# AMS_Slave_Controller.net
KiCad netlist of a schematic drawn in Altium Designer
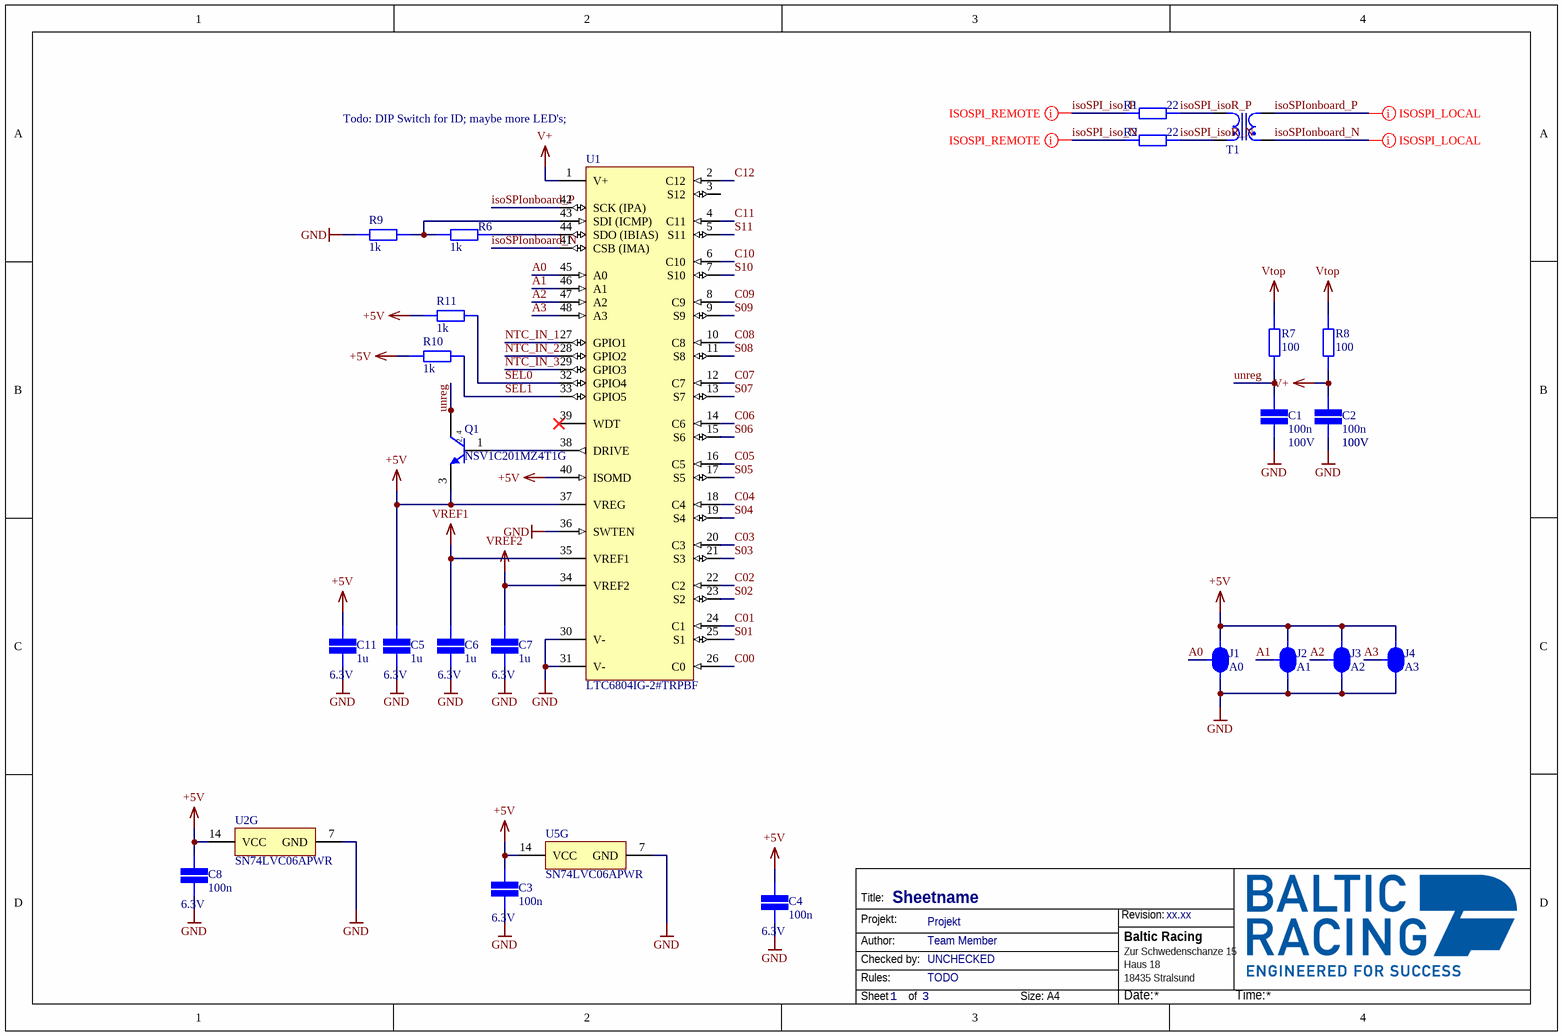
[diagram p0: AMS_Slave_Controller.SchDoc]

(export (version "E")
  (design (tool "Eeschema 10.0.6"))
  (components
    (comp (ref "C1")
      (value "100n")
      (footprint "CAP 0805/2012")
      (description "Capacitor with multiple Footprints")
      (fields (field (name "VOLTAGE") "100V") (field (name "Comment") "SMD Capacitor"))
      (libsource (lib "Standardbauteile") (part "SMD Capacitor"))
    )
    (comp (ref "C2")
      (value "100n")
      (footprint "CAP 0805/2012")
      (description "Capacitor with multiple Footprints")
      (fields (field (name "VOLTAGE") "100V") (field (name "Comment") "SMD Capacitor"))
      (libsource (lib "Standardbauteile") (part "SMD Capacitor"))
    )
    (comp (ref "C3")
      (value "100n")
      (footprint "CAP 0603/1608")
      (description "Capacitor with multiple Footprints")
      (fields (field (name "VOLTAGE") "6.3V") (field (name "Comment") "SMD Capacitor"))
      (libsource (lib "Standardbauteile") (part "SMD Capacitor"))
    )
    (comp (ref "C4")
      (value "100n")
      (footprint "CAP 0603/1608")
      (description "Capacitor with multiple Footprints")
      (fields (field (name "VOLTAGE") "6.3V") (field (name "Comment") "SMD Capacitor"))
      (libsource (lib "Standardbauteile") (part "SMD Capacitor"))
    )
    (comp (ref "C5")
      (value "1u")
      (footprint "CAP 0805/2012")
      (description "Capacitor with multiple Footprints")
      (fields (field (name "VOLTAGE") "6.3V") (field (name "Comment") "SMD Capacitor"))
      (libsource (lib "") (part "SMD Capacitor_1"))
    )
    (comp (ref "C6")
      (value "1u")
      (footprint "CAP 0805/2012")
      (description "Capacitor with multiple Footprints")
      (fields (field (name "VOLTAGE") "6.3V") (field (name "Comment") "SMD Capacitor"))
      (libsource (lib "") (part "SMD Capacitor_1"))
    )
    (comp (ref "C7")
      (value "1u")
      (footprint "CAP 0805/2012")
      (description "Capacitor with multiple Footprints")
      (fields (field (name "VOLTAGE") "6.3V") (field (name "Comment") "SMD Capacitor"))
      (libsource (lib "") (part "SMD Capacitor_1"))
    )
    (comp (ref "C8")
      (value "100n")
      (footprint "CAP 0603/1608")
      (description "Capacitor with multiple Footprints")
      (fields (field (name "VOLTAGE") "6.3V") (field (name "Comment") "SMD Capacitor"))
      (libsource (lib "Standardbauteile") (part "SMD Capacitor"))
    )
    (comp (ref "C11")
      (value "1u")
      (footprint "CAP 0805/2012")
      (description "Capacitor with multiple Footprints")
      (fields (field (name "VOLTAGE") "6.3V") (field (name "Comment") "SMD Capacitor"))
      (libsource (lib "") (part "SMD Capacitor_1"))
    )
    (comp (ref "J1")
      (value "A0")
      (footprint "SMD-JUMPER-3")
      (libsource (lib "Standardbauteile") (part "SMD Jumper 3"))
    )
    (comp (ref "J2")
      (value "A1")
      (footprint "SMD-JUMPER-3")
      (libsource (lib "Standardbauteile") (part "SMD Jumper 3"))
    )
    (comp (ref "J3")
      (value "A2")
      (footprint "SMD-JUMPER-3")
      (libsource (lib "Standardbauteile") (part "SMD Jumper 3"))
    )
    (comp (ref "J4")
      (value "A3")
      (footprint "SMD-JUMPER-3")
      (libsource (lib "Standardbauteile") (part "SMD Jumper 3"))
    )
    (comp (ref "Q1")
      (value "NSV1C201MZ4T1G")
      (footprint "ONSC-SOT-223-4-318E-04_V")
      (description "100 V, 2 A, Low VCE(sat), NPN Transistor, 4-Pin SOT-223, Pb-Free, Tape and Reel")
      (fields (field (name "MANUFACTURER") "On Semiconductor"))
      (libsource (lib "Altium Content Vault") (part "ONSC-NPN-B1C2E3C4-4"))
    )
    (comp (ref "R1")
      (value "22")
      (footprint "STACKPOLE CSR0603")
      (description "Resistor with multiple footprints")
      (fields (field (name "Comment") "SMD Resistor"))
      (libsource (lib "Standardbauteile") (part "SMD Resistor"))
    )
    (comp (ref "R2")
      (value "22")
      (footprint "STACKPOLE CSR0603")
      (description "Resistor with multiple footprints")
      (fields (field (name "Comment") "SMD Resistor"))
      (libsource (lib "Standardbauteile") (part "SMD Resistor"))
    )
    (comp (ref "R6")
      (value "1k")
      (footprint "STACKPOLE CSR0603")
      (description "Resistor with multiple footprints")
      (fields (field (name "Comment") "SMD Resistor"))
      (libsource (lib "Standardbauteile") (part "SMD Resistor"))
    )
    (comp (ref "R7")
      (value "100")
      (footprint "STACKPOLE CSR0603")
      (description "Resistor with multiple footprints")
      (fields (field (name "Comment") "SMD Resistor"))
      (libsource (lib "Standardbauteile") (part "SMD Resistor"))
    )
    (comp (ref "R8")
      (value "100")
      (footprint "STACKPOLE CSR0603")
      (description "Resistor with multiple footprints")
      (fields (field (name "Comment") "SMD Resistor"))
      (libsource (lib "Standardbauteile") (part "SMD Resistor"))
    )
    (comp (ref "R9")
      (value "1k")
      (footprint "STACKPOLE CSR0603")
      (description "Resistor with multiple footprints")
      (fields (field (name "Comment") "SMD Resistor"))
      (libsource (lib "Standardbauteile") (part "SMD Resistor"))
    )
    (comp (ref "R10")
      (value "1k")
      (footprint "STACKPOLE CSR0603")
      (description "Resistor with multiple footprints")
      (fields (field (name "Comment") "SMD Resistor"))
      (libsource (lib "Standardbauteile") (part "SMD Resistor"))
    )
    (comp (ref "R11")
      (value "1k")
      (footprint "STACKPOLE CSR0603")
      (description "Resistor with multiple footprints")
      (fields (field (name "Comment") "SMD Resistor"))
      (libsource (lib "Standardbauteile") (part "SMD Resistor"))
    )
    (comp (ref "T1")
      (value "750110055")
      (footprint "Wuerth_750110055")
      (description "Würth Toroid Transformer 1:1 70µH")
      (libsource (lib "Standardbauteile") (part "Wuerth_Transformer_750110055"))
    )
    (comp (ref "U1")
      (value "LTC6804IG-2#TRPBF")
      (footprint "LT-G-48_M")
      (description "Multicell Battery Monitor, 60 V Vin MAX, 48-pin SOP (G-48), -40 to 85 degC, Pb-Free, Tape and Reel")
      (fields (field (name "MANUFACTURER") "Linear Technology"))
      (libsource (lib "Altium Content Vault") (part "LT-LTC6804-2-G-48"))
    )
    (comp (ref "U2")
      (value "SN74LVC06APWR")
      (footprint "PW0014A_M")
      (description "Hex Inverter Buffers/Drivers With Open-Drain Outputs, PW0014A, LARGE T&R")
      (fields
        (field (name "GENERIC PART NUMBER") "SN74LVC06A")
        (field (name "MANUFACTURER") "Texas Instruments")
      )
      (libsource (lib "Altium Content Vault") (part "TI-CD_SNX4XXXXX05X_X6X-14"))
    )
    (comp (ref "U5")
      (value "SN74LVC06APWR")
      (footprint "PW0014A_M")
      (description "Hex Inverter Buffers/Drivers With Open-Drain Outputs, PW0014A, LARGE T&R")
      (fields
        (field (name "GENERIC PART NUMBER") "SN74LVC06A")
        (field (name "MANUFACTURER") "Texas Instruments")
      )
      (libsource (lib "Altium Content Vault") (part "TI-CD_SNX4XXXXX05X_X6X-14"))
    )
  )
  (nets
    (net (code "1") (name "+5V") (class "Default")
      (node (ref "C11") (pin "1") (pinfunction "1_1") (pintype "passive"))
      (node (ref "C3") (pin "2") (pinfunction "2_2") (pintype "passive"))
      (node (ref "C4") (pin "2") (pinfunction "2_2") (pintype "passive"))
      (node (ref "C5") (pin "1") (pinfunction "1_1") (pintype "passive"))
      (node (ref "C8") (pin "2") (pinfunction "2_2") (pintype "passive"))
      (node (ref "J1") (pin "3") (pinfunction "3_3") (pintype "passive"))
      (node (ref "J2") (pin "3") (pinfunction "3_3") (pintype "passive"))
      (node (ref "J3") (pin "3") (pinfunction "3_3") (pintype "passive"))
      (node (ref "J4") (pin "3") (pinfunction "3_3") (pintype "passive"))
      (node (ref "Q1") (pin "3") (pinfunction "E_3") (pintype "passive"))
      (node (ref "R10") (pin "1") (pinfunction "1_1") (pintype "passive"))
      (node (ref "R11") (pin "1") (pinfunction "1_1") (pintype "passive"))
      (node (ref "U1") (pin "37") (pinfunction "VREG_37") (pintype "power_in"))
      (node (ref "U1") (pin "40") (pinfunction "ISOMD_40") (pintype "input"))
      (node (ref "U2") (pin "14") (pinfunction "VCC_14") (pintype "power_in"))
      (node (ref "U5") (pin "14") (pinfunction "VCC_14") (pintype "power_in"))
    )
    (net (code "2") (name "/A0") (class "Default")
      (node (ref "J1") (pin "2") (pinfunction "2_2") (pintype "passive"))
      (node (ref "U1") (pin "45") (pinfunction "A0_45") (pintype "input"))
    )
    (net (code "3") (name "/A1") (class "Default")
      (node (ref "J2") (pin "2") (pinfunction "2_2") (pintype "passive"))
      (node (ref "U1") (pin "46") (pinfunction "A1_46") (pintype "input"))
    )
    (net (code "4") (name "/A2") (class "Default")
      (node (ref "J3") (pin "2") (pinfunction "2_2") (pintype "passive"))
      (node (ref "U1") (pin "47") (pinfunction "A2_47") (pintype "input"))
    )
    (net (code "5") (name "/A3") (class "Default")
      (node (ref "J4") (pin "2") (pinfunction "2_2") (pintype "passive"))
      (node (ref "U1") (pin "48") (pinfunction "A3_48") (pintype "input"))
    )
    (net (code "6") (name "/C00") (class "Default")
      (node (ref "U1") (pin "26") (pinfunction "C0_26") (pintype "input"))
    )
    (net (code "7") (name "/C01") (class "Default")
      (node (ref "U1") (pin "24") (pinfunction "C1_24") (pintype "input"))
    )
    (net (code "8") (name "/C02") (class "Default")
      (node (ref "U1") (pin "22") (pinfunction "C2_22") (pintype "input"))
    )
    (net (code "9") (name "/C03") (class "Default")
      (node (ref "U1") (pin "20") (pinfunction "C3_20") (pintype "input"))
    )
    (net (code "10") (name "/C04") (class "Default")
      (node (ref "U1") (pin "18") (pinfunction "C4_18") (pintype "input"))
    )
    (net (code "11") (name "/C05") (class "Default")
      (node (ref "U1") (pin "16") (pinfunction "C5_16") (pintype "input"))
    )
    (net (code "12") (name "/C06") (class "Default")
      (node (ref "U1") (pin "14") (pinfunction "C6_14") (pintype "input"))
    )
    (net (code "13") (name "/C07") (class "Default")
      (node (ref "U1") (pin "12") (pinfunction "C7_12") (pintype "input"))
    )
    (net (code "14") (name "/C08") (class "Default")
      (node (ref "U1") (pin "10") (pinfunction "C8_10") (pintype "input"))
    )
    (net (code "15") (name "/C09") (class "Default")
      (node (ref "U1") (pin "8") (pinfunction "C9_8") (pintype "input"))
    )
    (net (code "16") (name "/C10") (class "Default")
      (node (ref "U1") (pin "6") (pinfunction "C10_6") (pintype "input"))
    )
    (net (code "17") (name "/C11") (class "Default")
      (node (ref "U1") (pin "4") (pinfunction "C11_4") (pintype "input"))
    )
    (net (code "18") (name "/C12") (class "Default")
      (node (ref "U1") (pin "2") (pinfunction "C12_2") (pintype "input"))
    )
    (net (code "19") (name "/NTC_IN_1") (class "Default")
      (node (ref "U1") (pin "27") (pinfunction "GPIO1_27") (pintype "bidirectional"))
    )
    (net (code "20") (name "/NTC_IN_2") (class "Default")
      (node (ref "U1") (pin "28") (pinfunction "GPIO2_28") (pintype "bidirectional"))
    )
    (net (code "21") (name "/NTC_IN_3") (class "Default")
      (node (ref "U1") (pin "29") (pinfunction "GPIO3_29") (pintype "bidirectional"))
    )
    (net (code "22") (name "/S01") (class "Default")
      (node (ref "U1") (pin "25") (pinfunction "S1_25") (pintype "bidirectional"))
    )
    (net (code "23") (name "/S02") (class "Default")
      (node (ref "U1") (pin "23") (pinfunction "S2_23") (pintype "bidirectional"))
    )
    (net (code "24") (name "/S03") (class "Default")
      (node (ref "U1") (pin "21") (pinfunction "S3_21") (pintype "bidirectional"))
    )
    (net (code "25") (name "/S04") (class "Default")
      (node (ref "U1") (pin "19") (pinfunction "S4_19") (pintype "bidirectional"))
    )
    (net (code "26") (name "/S05") (class "Default")
      (node (ref "U1") (pin "17") (pinfunction "S5_17") (pintype "bidirectional"))
    )
    (net (code "27") (name "/S06") (class "Default")
      (node (ref "U1") (pin "15") (pinfunction "S6_15") (pintype "bidirectional"))
    )
    (net (code "28") (name "/S07") (class "Default")
      (node (ref "U1") (pin "13") (pinfunction "S7_13") (pintype "bidirectional"))
    )
    (net (code "29") (name "/S08") (class "Default")
      (node (ref "U1") (pin "11") (pinfunction "S8_11") (pintype "bidirectional"))
    )
    (net (code "30") (name "/S09") (class "Default")
      (node (ref "U1") (pin "9") (pinfunction "S9_9") (pintype "bidirectional"))
    )
    (net (code "31") (name "/S10") (class "Default")
      (node (ref "U1") (pin "7") (pinfunction "S10_7") (pintype "bidirectional"))
    )
    (net (code "32") (name "/S11") (class "Default")
      (node (ref "U1") (pin "5") (pinfunction "S11_5") (pintype "bidirectional"))
    )
    (net (code "33") (name "/SEL0") (class "Default")
      (node (ref "R11") (pin "2") (pinfunction "2_2") (pintype "passive"))
      (node (ref "U1") (pin "32") (pinfunction "GPIO4_32") (pintype "bidirectional"))
    )
    (net (code "34") (name "/SEL1") (class "Default")
      (node (ref "R10") (pin "2") (pinfunction "2_2") (pintype "passive"))
      (node (ref "U1") (pin "33") (pinfunction "GPIO5_33") (pintype "bidirectional"))
    )
    (net (code "35") (name "/isoSPI_isoR_N") (class "Default")
      (node (ref "R2") (pin "2") (pinfunction "2_2") (pintype "passive"))
      (node (ref "T1") (pin "1") (pinfunction "1_1") (pintype "passive"))
    )
    (net (code "36") (name "/isoSPI_isoR_P") (class "Default")
      (node (ref "R1") (pin "2") (pinfunction "2_2") (pintype "passive"))
      (node (ref "T1") (pin "2") (pinfunction "2_2") (pintype "passive"))
    )
    (net (code "37") (name "/isoSPI_iso_N") (class "Default")
      (node (ref "R2") (pin "1") (pinfunction "1_1") (pintype "passive"))
    )
    (net (code "38") (name "/isoSPI_iso_P") (class "Default")
      (node (ref "R1") (pin "1") (pinfunction "1_1") (pintype "passive"))
    )
    (net (code "39") (name "/isoSPIonboard_N") (class "Default")
      (node (ref "T1") (pin "4") (pinfunction "4_4") (pintype "passive"))
      (node (ref "U1") (pin "41") (pinfunction "CSB_(IMA)_41") (pintype "bidirectional"))
    )
    (net (code "40") (name "/isoSPIonboard_P") (class "Default")
      (node (ref "T1") (pin "3") (pinfunction "3_3") (pintype "passive"))
      (node (ref "U1") (pin "42") (pinfunction "SCK_(IPA)_42") (pintype "bidirectional"))
    )
    (net (code "41") (name "/unreg") (class "Default")
      (node (ref "C1") (pin "2") (pinfunction "2_2") (pintype "passive"))
      (node (ref "Q1") (pin "2") (pinfunction "C_2") (pintype "passive"))
      (node (ref "Q1") (pin "4") (pinfunction "C_4") (pintype "passive"))
      (node (ref "R7") (pin "1") (pinfunction "1_1") (pintype "passive"))
    )
    (net (code "42") (name "GND") (class "Default")
      (node (ref "C1") (pin "1") (pinfunction "1_1") (pintype "passive"))
      (node (ref "C11") (pin "2") (pinfunction "2_2") (pintype "passive"))
      (node (ref "C2") (pin "1") (pinfunction "1_1") (pintype "passive"))
      (node (ref "C3") (pin "1") (pinfunction "1_1") (pintype "passive"))
      (node (ref "C4") (pin "1") (pinfunction "1_1") (pintype "passive"))
      (node (ref "C5") (pin "2") (pinfunction "2_2") (pintype "passive"))
      (node (ref "C6") (pin "2") (pinfunction "2_2") (pintype "passive"))
      (node (ref "C7") (pin "2") (pinfunction "2_2") (pintype "passive"))
      (node (ref "C8") (pin "1") (pinfunction "1_1") (pintype "passive"))
      (node (ref "J1") (pin "1") (pinfunction "1_1") (pintype "passive"))
      (node (ref "J2") (pin "1") (pinfunction "1_1") (pintype "passive"))
      (node (ref "J3") (pin "1") (pinfunction "1_1") (pintype "passive"))
      (node (ref "J4") (pin "1") (pinfunction "1_1") (pintype "passive"))
      (node (ref "R9") (pin "2") (pinfunction "2_2") (pintype "passive"))
      (node (ref "U1") (pin "30") (pinfunction "V-_30") (pintype "power_in"))
      (node (ref "U1") (pin "31") (pinfunction "V-_31") (pintype "power_in"))
      (node (ref "U1") (pin "36") (pinfunction "SWTEN_36") (pintype "input"))
      (node (ref "U2") (pin "7") (pinfunction "GND_7") (pintype "power_in"))
      (node (ref "U5") (pin "7") (pinfunction "GND_7") (pintype "power_in"))
    )
    (net (code "43") (name "Net-(Q1-B)") (class "Default")
      (node (ref "Q1") (pin "1") (pinfunction "B_1") (pintype "passive"))
      (node (ref "U1") (pin "38") (pinfunction "DRIVE_38") (pintype "output"))
    )
    (net (code "44") (name "Net-(U1-SDI_(ICMP))") (class "Default")
      (node (ref "R6") (pin "2") (pinfunction "2_2") (pintype "passive"))
      (node (ref "R9") (pin "1") (pinfunction "1_1") (pintype "passive"))
      (node (ref "U1") (pin "43") (pinfunction "SDI_(ICMP)_43") (pintype "input"))
    )
    (net (code "45") (name "Net-(U1-SDO_(IBIAS))") (class "Default")
      (node (ref "R6") (pin "1") (pinfunction "1_1") (pintype "passive"))
      (node (ref "U1") (pin "44") (pinfunction "SDO_(IBIAS)_44") (pintype "bidirectional"))
    )
    (net (code "46") (name "V+") (class "Default")
      (node (ref "C2") (pin "2") (pinfunction "2_2") (pintype "passive"))
      (node (ref "R8") (pin "1") (pinfunction "1_1") (pintype "passive"))
      (node (ref "U1") (pin "1") (pinfunction "V+_1") (pintype "power_in"))
    )
    (net (code "47") (name "VREF1") (class "Default")
      (node (ref "C6") (pin "1") (pinfunction "1_1") (pintype "passive"))
      (node (ref "U1") (pin "35") (pinfunction "VREF1_35") (pintype "passive"))
    )
    (net (code "48") (name "VREF2") (class "Default")
      (node (ref "C7") (pin "1") (pinfunction "1_1") (pintype "passive"))
      (node (ref "U1") (pin "34") (pinfunction "VREF2_34") (pintype "passive"))
    )
    (net (code "49") (name "Vtop") (class "Default")
      (node (ref "R7") (pin "2") (pinfunction "2_2") (pintype "passive"))
      (node (ref "R8") (pin "2") (pinfunction "2_2") (pintype "passive"))
    )
    (net (code "50") (name "unconnected-(U1-S12-Pad3)") (class "Default")
      (node (ref "U1") (pin "3") (pinfunction "S12_3") (pintype "bidirectional"))
    )
    (net (code "51") (name "unconnected-(U1-WDT-Pad39)") (class "Default")
      (node (ref "U1") (pin "39") (pinfunction "WDT_39") (pintype "tri_state+no_connect"))
    )
  )
)
